# Terrarium.net
KiCad netlist of a schematic drawn in EAGLE
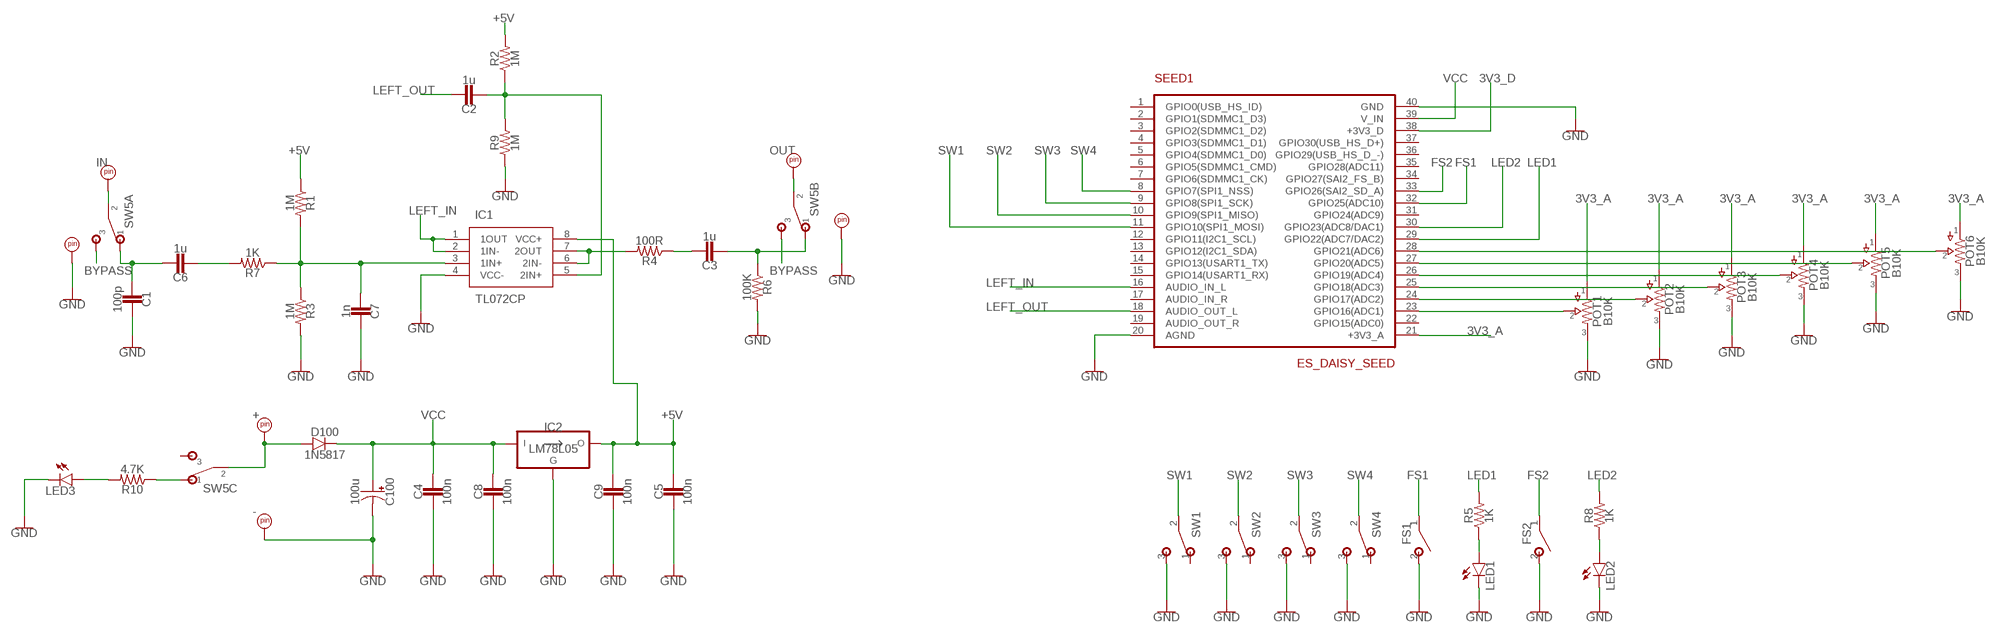
[diagram p0: schematic, sheet 1]

(export (version "E")
  (design (tool "Eeschema 10.0.6"))
  (components
    (comp (ref "C1")
      (value "100p")
      (footprint "eagle-import:5MM")
      (libsource (lib "eagle-import") (part "CAP.2"))
    )
    (comp (ref "C2")
      (value "1u")
      (footprint "eagle-import:.33UF+")
      (libsource (lib "eagle-import") (part "CAP.5"))
    )
    (comp (ref "C3")
      (value "1u")
      (footprint "eagle-import:.33UF+")
      (libsource (lib "eagle-import") (part "CAP.5"))
    )
    (comp (ref "C4")
      (value "100n")
      (footprint "eagle-import:5MM")
      (libsource (lib "eagle-import") (part "CAP.2"))
    )
    (comp (ref "C5")
      (value "100n")
      (footprint "eagle-import:5MM")
      (libsource (lib "eagle-import") (part "CAP.2"))
    )
    (comp (ref "C6")
      (value "1u")
      (footprint "eagle-import:.33UF+")
      (libsource (lib "eagle-import") (part "CAP.5"))
    )
    (comp (ref "C7")
      (value "1n")
      (footprint "eagle-import:5MM")
      (libsource (lib "eagle-import") (part "CAP.2"))
    )
    (comp (ref "C8")
      (value "100n")
      (footprint "eagle-import:5MM")
      (libsource (lib "eagle-import") (part "CAP.2"))
    )
    (comp (ref "C9")
      (value "100n")
      (footprint "eagle-import:5MM")
      (libsource (lib "eagle-import") (part "CAP.2"))
    )
    (comp (ref "C100")
      (value "100u")
      (footprint "eagle-import:050_2.5MM.2")
      (libsource (lib "eagle-import") (part "5.0_MM.4"))
    )
    (comp (ref "D100")
      (value "1N5817")
      (footprint "eagle-import:DO41-3")
      (libsource (lib "eagle-import") (part "DO41.3"))
    )
    (comp (ref "FS1")
      (value "SPST")
      (footprint "eagle-import:SPST")
      (libsource (lib "eagle-import") (part "SPST"))
    )
    (comp (ref "FS2")
      (value "SPST")
      (footprint "eagle-import:SPST")
      (libsource (lib "eagle-import") (part "SPST"))
    )
    (comp (ref "GND")
      (value "PADRD")
      (footprint "eagle-import:UNLABELED")
      (fields (field (name "NM") "-"))
      (libsource (lib "eagle-import") (part "PADRD"))
    )
    (comp (ref "IC1")
      (value "TL072CP")
      (footprint "eagle-import:DIP794W53P254L959H508Q8N")
      (fields (field (name "MOUSER_PART_NUMBER") "595-TL072CP"))
      (libsource (lib "eagle-import") (part "TL072CP"))
    )
    (comp (ref "IC2")
      (value "LM78L05")
      (footprint "eagle-import:TO92-")
      (libsource (lib "eagle-import") (part "LM78L05"))
    )
    (comp (ref "IN")
      (value "PADRD")
      (footprint "eagle-import:UNLABELED")
      (fields (field (name "NM") "IN"))
      (libsource (lib "eagle-import") (part "PADRD"))
    )
    (comp (ref "IN_GND")
      (value "PADRD")
      (footprint "eagle-import:UNLABELED")
      (libsource (lib "eagle-import") (part "PADRD"))
    )
    (comp (ref "LED1")
      (value "LED.3")
      (footprint "eagle-import:3MM_2")
      (libsource (lib "eagle-import") (part "LED.3"))
    )
    (comp (ref "LED2")
      (value "LED.3")
      (footprint "eagle-import:3MM_2")
      (libsource (lib "eagle-import") (part "LED.3"))
    )
    (comp (ref "LED3")
      (value "LED.3")
      (footprint "eagle-import:3MM_2")
      (libsource (lib "eagle-import") (part "LED.3"))
    )
    (comp (ref "OUT")
      (value "PADRD")
      (footprint "eagle-import:UNLABELED")
      (fields (field (name "NM") "OUT"))
      (libsource (lib "eagle-import") (part "PADRD"))
    )
    (comp (ref "OUT_GND")
      (value "PADRD")
      (footprint "eagle-import:UNLABELED")
      (libsource (lib "eagle-import") (part "PADRD"))
    )
    (comp (ref "POT1")
      (value "B10K")
      (footprint "eagle-import:16MM_PADS.2")
      (libsource (lib "eagle-import") (part "16MM.5"))
    )
    (comp (ref "POT2")
      (value "B10K")
      (footprint "eagle-import:16MM_PADS.2")
      (libsource (lib "eagle-import") (part "16MM.5"))
    )
    (comp (ref "POT3")
      (value "B10K")
      (footprint "eagle-import:16MM_PADS.2")
      (libsource (lib "eagle-import") (part "16MM.5"))
    )
    (comp (ref "POT4")
      (value "B10K")
      (footprint "eagle-import:16MM_PADS.2")
      (libsource (lib "eagle-import") (part "16MM.5"))
    )
    (comp (ref "POT5")
      (value "B10K")
      (footprint "eagle-import:16MM_PADS.2")
      (libsource (lib "eagle-import") (part "16MM.5"))
    )
    (comp (ref "POT6")
      (value "B10K")
      (footprint "eagle-import:16MM_PADS.2")
      (libsource (lib "eagle-import") (part "16MM.5"))
    )
    (comp (ref "PWR")
      (value "PADRD")
      (footprint "eagle-import:UNLABELED")
      (fields (field (name "NM") "+"))
      (libsource (lib "eagle-import") (part "PADRD"))
    )
    (comp (ref "R1")
      (value "1M")
      (footprint "eagle-import:7.5MM.2")
      (libsource (lib "eagle-import") (part "R.3B"))
    )
    (comp (ref "R2")
      (value "1M")
      (footprint "eagle-import:7.5MM.2")
      (libsource (lib "eagle-import") (part "R.3B"))
    )
    (comp (ref "R3")
      (value "1M")
      (footprint "eagle-import:7.5MM.2")
      (libsource (lib "eagle-import") (part "R.3B"))
    )
    (comp (ref "R4")
      (value "100R")
      (footprint "eagle-import:7.5MM.2")
      (libsource (lib "eagle-import") (part "R.3B"))
    )
    (comp (ref "R5")
      (value "1K")
      (footprint "eagle-import:7.5MM.2")
      (libsource (lib "eagle-import") (part "R.3B"))
    )
    (comp (ref "R6")
      (value "100K")
      (footprint "eagle-import:7.5MM.2")
      (libsource (lib "eagle-import") (part "R.3B"))
    )
    (comp (ref "R7")
      (value "1K")
      (footprint "eagle-import:7.5MM.2")
      (libsource (lib "eagle-import") (part "R.3B"))
    )
    (comp (ref "R8")
      (value "1K")
      (footprint "eagle-import:7.5MM.2")
      (libsource (lib "eagle-import") (part "R.3B"))
    )
    (comp (ref "R9")
      (value "1M")
      (footprint "eagle-import:7.5MM.2")
      (libsource (lib "eagle-import") (part "R.3B"))
    )
    (comp (ref "R10")
      (value "4.7K")
      (footprint "eagle-import:7.5MM.2")
      (libsource (lib "eagle-import") (part "R.3B"))
    )
    (comp (ref "SEED1")
      (value "ES_DAISY_SEED")
      (footprint "eagle-import:ES_DAISY_SEED")
      (libsource (lib "eagle-import") (part "ES_DAISY_SEED"))
    )
    (comp (ref "SW1")
      (value "SPDT.1")
      (footprint "eagle-import:SPDT_SOLDER_LUG")
      (libsource (lib "eagle-import") (part "SPDT.1"))
    )
    (comp (ref "SW2")
      (value "SPDT.1")
      (footprint "eagle-import:SPDT_SOLDER_LUG")
      (libsource (lib "eagle-import") (part "SPDT.1"))
    )
    (comp (ref "SW3")
      (value "SPDT.1")
      (footprint "eagle-import:SPDT_SOLDER_LUG")
      (libsource (lib "eagle-import") (part "SPDT.1"))
    )
    (comp (ref "SW4")
      (value "SPDT.1")
      (footprint "eagle-import:SPDT_SOLDER_LUG")
      (libsource (lib "eagle-import") (part "SPDT.1"))
    )
    (comp (ref "SW5")
      (value "3PDTTOGGLE")
      (footprint "eagle-import:3PDT2")
      (libsource (lib "eagle-import") (part "3PDTTOGGLE"))
    )
  )
  (nets
    (net (code "1") (name "/+5V") (class "Default")
      (node (ref "C5") (pin "1") (pinfunction "1_1") (pintype "passive"))
      (node (ref "C9") (pin "1") (pinfunction "1_1") (pintype "passive"))
      (node (ref "IC1") (pin "8") (pinfunction "VCC+_8") (pintype "bidirectional"))
      (node (ref "IC2") (pin "3") (pinfunction "VO_3") (pintype "passive"))
      (node (ref "R1") (pin "1") (pinfunction "1_1") (pintype "passive"))
      (node (ref "R2") (pin "2") (pinfunction "2_2") (pintype "passive"))
    )
    (net (code "2") (name "/3V3_A") (class "Default")
      (node (ref "POT1") (pin "1") (pinfunction "1_1") (pintype "passive"))
      (node (ref "POT2") (pin "1") (pinfunction "1_1") (pintype "passive"))
      (node (ref "POT3") (pin "1") (pinfunction "1_1") (pintype "passive"))
      (node (ref "POT4") (pin "1") (pinfunction "1_1") (pintype "passive"))
      (node (ref "POT5") (pin "1") (pinfunction "1_1") (pintype "passive"))
      (node (ref "POT6") (pin "1") (pinfunction "1_1") (pintype "passive"))
      (node (ref "SEED1") (pin "21") (pinfunction "+3V3_A_21") (pintype "bidirectional"))
    )
    (net (code "3") (name "/3V3_D") (class "Default")
      (node (ref "SEED1") (pin "38") (pinfunction "+3V3_D_38") (pintype "bidirectional"))
    )
    (net (code "4") (name "/BYPASS") (class "Default")
      (node (ref "SW5") (pin "A3") (pinfunction "3_A3") (pintype "passive"))
      (node (ref "SW5") (pin "B3") (pinfunction "3_B3") (pintype "passive"))
    )
    (net (code "5") (name "/FS1") (class "Default")
      (node (ref "FS1") (pin "1") (pinfunction "P_1") (pintype "passive"))
      (node (ref "SEED1") (pin "32") (pinfunction "GPIO25(ADC10)_32") (pintype "bidirectional"))
    )
    (net (code "6") (name "/FS2") (class "Default")
      (node (ref "FS2") (pin "1") (pinfunction "P_1") (pintype "passive"))
      (node (ref "SEED1") (pin "33") (pinfunction "GPIO26(SAI2_SD_A)_33") (pintype "bidirectional"))
    )
    (net (code "7") (name "/LED1") (class "Default")
      (node (ref "R5") (pin "2") (pinfunction "2_2") (pintype "passive"))
      (node (ref "SEED1") (pin "29") (pinfunction "GPIO22(ADC7/DAC2)_29") (pintype "bidirectional"))
    )
    (net (code "8") (name "/LED2") (class "Default")
      (node (ref "R8") (pin "2") (pinfunction "2_2") (pintype "passive"))
      (node (ref "SEED1") (pin "30") (pinfunction "GPIO23(ADC8/DAC1)_30") (pintype "bidirectional"))
    )
    (net (code "9") (name "/LEFT_IN") (class "Default")
      (node (ref "IC1") (pin "1") (pinfunction "1OUT_1") (pintype "bidirectional"))
      (node (ref "IC1") (pin "2") (pinfunction "1IN-_2") (pintype "bidirectional"))
      (node (ref "SEED1") (pin "16") (pinfunction "AUDIO_IN_L_16") (pintype "bidirectional"))
    )
    (net (code "10") (name "/LEFT_OUT") (class "Default")
      (node (ref "C2") (pin "1") (pinfunction "1_1") (pintype "passive"))
      (node (ref "SEED1") (pin "18") (pinfunction "AUDIO_OUT_L_18") (pintype "bidirectional"))
    )
    (net (code "11") (name "/SW1") (class "Default")
      (node (ref "SEED1") (pin "11") (pinfunction "GPIO10(SPI1_MOSI)_11") (pintype "bidirectional"))
      (node (ref "SW1") (pin "2") (pinfunction "P_2") (pintype "passive"))
    )
    (net (code "12") (name "/SW2") (class "Default")
      (node (ref "SEED1") (pin "10") (pinfunction "GPIO9(SPI1_MISO)_10") (pintype "bidirectional"))
      (node (ref "SW2") (pin "2") (pinfunction "P_2") (pintype "passive"))
    )
    (net (code "13") (name "/SW3") (class "Default")
      (node (ref "SEED1") (pin "9") (pinfunction "GPIO8(SPI1_SCK)_9") (pintype "bidirectional"))
      (node (ref "SW3") (pin "2") (pinfunction "P_2") (pintype "passive"))
    )
    (net (code "14") (name "/SW4") (class "Default")
      (node (ref "SEED1") (pin "8") (pinfunction "GPIO7(SPI1_NSS)_8") (pintype "bidirectional"))
      (node (ref "SW4") (pin "2") (pinfunction "P_2") (pintype "passive"))
    )
    (net (code "15") (name "/VCC") (class "Default")
      (node (ref "C100") (pin "+") (pinfunction "+_+") (pintype "passive"))
      (node (ref "C4") (pin "1") (pinfunction "1_1") (pintype "passive"))
      (node (ref "C8") (pin "1") (pinfunction "1_1") (pintype "passive"))
      (node (ref "D100") (pin "C") (pinfunction "C_C") (pintype "passive"))
      (node (ref "IC2") (pin "1") (pinfunction "VI_1") (pintype "input"))
      (node (ref "SEED1") (pin "39") (pinfunction "V_IN_39") (pintype "bidirectional"))
    )
    (net (code "16") (name "GND") (class "Default")
      (node (ref "C1") (pin "1") (pinfunction "1_1") (pintype "passive"))
      (node (ref "C100") (pin "-") (pinfunction "-_-") (pintype "passive"))
      (node (ref "C4") (pin "2") (pinfunction "2_2") (pintype "passive"))
      (node (ref "C5") (pin "2") (pinfunction "2_2") (pintype "passive"))
      (node (ref "C7") (pin "1") (pinfunction "1_1") (pintype "passive"))
      (node (ref "C8") (pin "2") (pinfunction "2_2") (pintype "passive"))
      (node (ref "C9") (pin "2") (pinfunction "2_2") (pintype "passive"))
      (node (ref "FS1") (pin "2") (pinfunction "S_2") (pintype "passive"))
      (node (ref "FS2") (pin "2") (pinfunction "S_2") (pintype "passive"))
      (node (ref "GND") (pin "P$1") (pinfunction "P$1_P$1") (pintype "bidirectional"))
      (node (ref "IC1") (pin "4") (pinfunction "VCC-_4") (pintype "bidirectional"))
      (node (ref "IC2") (pin "2") (pinfunction "GND_2") (pintype "passive"))
      (node (ref "IN_GND") (pin "P$1") (pinfunction "P$1_P$1") (pintype "bidirectional"))
      (node (ref "LED1") (pin "P$1") (pinfunction "C_P$1") (pintype "passive"))
      (node (ref "LED2") (pin "P$1") (pinfunction "C_P$1") (pintype "passive"))
      (node (ref "LED3") (pin "P$1") (pinfunction "C_P$1") (pintype "passive"))
      (node (ref "OUT_GND") (pin "P$1") (pinfunction "P$1_P$1") (pintype "bidirectional"))
      (node (ref "POT1") (pin "3") (pinfunction "3_3") (pintype "passive"))
      (node (ref "POT2") (pin "3") (pinfunction "3_3") (pintype "passive"))
      (node (ref "POT3") (pin "3") (pinfunction "3_3") (pintype "passive"))
      (node (ref "POT4") (pin "3") (pinfunction "3_3") (pintype "passive"))
      (node (ref "POT5") (pin "3") (pinfunction "3_3") (pintype "passive"))
      (node (ref "POT6") (pin "3") (pinfunction "3_3") (pintype "passive"))
      (node (ref "R3") (pin "2") (pinfunction "2_2") (pintype "passive"))
      (node (ref "R6") (pin "2") (pinfunction "2_2") (pintype "passive"))
      (node (ref "R9") (pin "1") (pinfunction "1_1") (pintype "passive"))
      (node (ref "SEED1") (pin "20") (pinfunction "AGND_20") (pintype "bidirectional"))
      (node (ref "SEED1") (pin "40") (pinfunction "GND_40") (pintype "bidirectional"))
      (node (ref "SW1") (pin "3") (pinfunction "S_3") (pintype "passive"))
      (node (ref "SW2") (pin "3") (pinfunction "S_3") (pintype "passive"))
      (node (ref "SW3") (pin "3") (pinfunction "S_3") (pintype "passive"))
      (node (ref "SW4") (pin "3") (pinfunction "S_3") (pintype "passive"))
    )
    (net (code "17") (name "Net-(C3-Pad1)") (class "Default")
      (node (ref "C3") (pin "1") (pinfunction "1_1") (pintype "passive"))
      (node (ref "R4") (pin "1") (pinfunction "1_1") (pintype "passive"))
    )
    (net (code "18") (name "Net-(C6-Pad2)") (class "Default")
      (node (ref "C6") (pin "2") (pinfunction "2_2") (pintype "passive"))
      (node (ref "R7") (pin "2") (pinfunction "2_2") (pintype "passive"))
    )
    (net (code "19") (name "Net-(IC1-1IN+)") (class "Default")
      (node (ref "C7") (pin "2") (pinfunction "2_2") (pintype "passive"))
      (node (ref "IC1") (pin "3") (pinfunction "1IN+_3") (pintype "bidirectional"))
      (node (ref "R1") (pin "2") (pinfunction "2_2") (pintype "passive"))
      (node (ref "R3") (pin "1") (pinfunction "1_1") (pintype "passive"))
      (node (ref "R7") (pin "1") (pinfunction "1_1") (pintype "passive"))
    )
    (net (code "20") (name "Net-(IC1-2IN+)") (class "Default")
      (node (ref "C2") (pin "2") (pinfunction "2_2") (pintype "passive"))
      (node (ref "IC1") (pin "5") (pinfunction "2IN+_5") (pintype "bidirectional"))
      (node (ref "R2") (pin "1") (pinfunction "1_1") (pintype "passive"))
      (node (ref "R9") (pin "2") (pinfunction "2_2") (pintype "passive"))
    )
    (net (code "21") (name "Net-(IC1-2IN-)") (class "Default")
      (node (ref "IC1") (pin "6") (pinfunction "2IN-_6") (pintype "bidirectional"))
      (node (ref "IC1") (pin "7") (pinfunction "2OUT_7") (pintype "bidirectional"))
      (node (ref "R4") (pin "2") (pinfunction "2_2") (pintype "passive"))
    )
    (net (code "22") (name "Net-(LED1-A)") (class "Default")
      (node (ref "LED1") (pin "ANODE") (pinfunction "A_ANODE") (pintype "passive"))
      (node (ref "R5") (pin "1") (pinfunction "1_1") (pintype "passive"))
    )
    (net (code "23") (name "Net-(LED2-A)") (class "Default")
      (node (ref "LED2") (pin "ANODE") (pinfunction "A_ANODE") (pintype "passive"))
      (node (ref "R8") (pin "1") (pinfunction "1_1") (pintype "passive"))
    )
    (net (code "24") (name "Net-(LED3-A)") (class "Default")
      (node (ref "LED3") (pin "ANODE") (pinfunction "A_ANODE") (pintype "passive"))
      (node (ref "R10") (pin "2") (pinfunction "2_2") (pintype "passive"))
    )
    (net (code "25") (name "Net-(SEED1-GPIO16(ADC1))") (class "Default")
      (node (ref "POT1") (pin "2") (pinfunction "2_2") (pintype "passive"))
      (node (ref "SEED1") (pin "23") (pinfunction "GPIO16(ADC1)_23") (pintype "bidirectional"))
    )
    (net (code "26") (name "Net-(SEED1-GPIO17(ADC2))") (class "Default")
      (node (ref "POT2") (pin "2") (pinfunction "2_2") (pintype "passive"))
      (node (ref "SEED1") (pin "24") (pinfunction "GPIO17(ADC2)_24") (pintype "bidirectional"))
    )
    (net (code "27") (name "Net-(SEED1-GPIO18(ADC3))") (class "Default")
      (node (ref "POT3") (pin "2") (pinfunction "2_2") (pintype "passive"))
      (node (ref "SEED1") (pin "25") (pinfunction "GPIO18(ADC3)_25") (pintype "bidirectional"))
    )
    (net (code "28") (name "Net-(SEED1-GPIO19(ADC4))") (class "Default")
      (node (ref "POT4") (pin "2") (pinfunction "2_2") (pintype "passive"))
      (node (ref "SEED1") (pin "26") (pinfunction "GPIO19(ADC4)_26") (pintype "bidirectional"))
    )
    (net (code "29") (name "Net-(SEED1-GPIO20(ADC5))") (class "Default")
      (node (ref "POT5") (pin "2") (pinfunction "2_2") (pintype "passive"))
      (node (ref "SEED1") (pin "27") (pinfunction "GPIO20(ADC5)_27") (pintype "bidirectional"))
    )
    (net (code "30") (name "Net-(SEED1-GPIO21(ADC6))") (class "Default")
      (node (ref "POT6") (pin "2") (pinfunction "2_2") (pintype "passive"))
      (node (ref "SEED1") (pin "28") (pinfunction "GPIO21(ADC6)_28") (pintype "bidirectional"))
    )
    (net (code "31") (name "Net-(SW5A-1)") (class "Default")
      (node (ref "C1") (pin "2") (pinfunction "2_2") (pintype "passive"))
      (node (ref "C6") (pin "1") (pinfunction "1_1") (pintype "passive"))
      (node (ref "SW5") (pin "A1") (pinfunction "1_A1") (pintype "passive"))
    )
    (net (code "32") (name "Net-(SW5A-2)") (class "Default")
      (node (ref "IN") (pin "P$1") (pinfunction "P$1_P$1") (pintype "bidirectional"))
      (node (ref "SW5") (pin "A2") (pinfunction "2_A2") (pintype "passive"))
    )
    (net (code "33") (name "Net-(SW5B-1)") (class "Default")
      (node (ref "C3") (pin "2") (pinfunction "2_2") (pintype "passive"))
      (node (ref "R6") (pin "1") (pinfunction "1_1") (pintype "passive"))
      (node (ref "SW5") (pin "B1") (pinfunction "1_B1") (pintype "passive"))
    )
    (net (code "34") (name "Net-(SW5B-2)") (class "Default")
      (node (ref "OUT") (pin "P$1") (pinfunction "P$1_P$1") (pintype "bidirectional"))
      (node (ref "SW5") (pin "B2") (pinfunction "2_B2") (pintype "passive"))
    )
    (net (code "35") (name "Net-(SW5C-1)") (class "Default")
      (node (ref "R10") (pin "1") (pinfunction "1_1") (pintype "passive"))
      (node (ref "SW5") (pin "C1") (pinfunction "1_C1") (pintype "passive"))
    )
    (net (code "36") (name "Net-(SW5C-2)") (class "Default")
      (node (ref "D100") (pin "A") (pinfunction "A_A") (pintype "passive"))
      (node (ref "PWR") (pin "P$1") (pinfunction "P$1_P$1") (pintype "bidirectional"))
      (node (ref "SW5") (pin "C2") (pinfunction "2_C2") (pintype "passive"))
    )
    (net (code "37") (name "unconnected-(SEED1-AUDIO_IN_R-Pad17)") (class "Default")
      (node (ref "SEED1") (pin "17") (pinfunction "AUDIO_IN_R_17") (pintype "bidirectional"))
    )
    (net (code "38") (name "unconnected-(SEED1-AUDIO_OUT_R-Pad19)") (class "Default")
      (node (ref "SEED1") (pin "19") (pinfunction "AUDIO_OUT_R_19") (pintype "bidirectional"))
    )
    (net (code "39") (name "unconnected-(SEED1-GPIO0(USB_HS_ID)-Pad1)") (class "Default")
      (node (ref "SEED1") (pin "1") (pinfunction "GPIO0(USB_HS_ID)_1") (pintype "bidirectional"))
    )
    (net (code "40") (name "unconnected-(SEED1-GPIO1(SDMMC1_D3)-Pad2)") (class "Default")
      (node (ref "SEED1") (pin "2") (pinfunction "GPIO1(SDMMC1_D3)_2") (pintype "bidirectional"))
    )
    (net (code "41") (name "unconnected-(SEED1-GPIO2(SDMMC1_D2)-Pad3)") (class "Default")
      (node (ref "SEED1") (pin "3") (pinfunction "GPIO2(SDMMC1_D2)_3") (pintype "bidirectional"))
    )
    (net (code "42") (name "unconnected-(SEED1-GPIO3(SDMMC1_D1)-Pad4)") (class "Default")
      (node (ref "SEED1") (pin "4") (pinfunction "GPIO3(SDMMC1_D1)_4") (pintype "bidirectional"))
    )
    (net (code "43") (name "unconnected-(SEED1-GPIO4(SDMMC1_D0)-Pad5)") (class "Default")
      (node (ref "SEED1") (pin "5") (pinfunction "GPIO4(SDMMC1_D0)_5") (pintype "bidirectional"))
    )
    (net (code "44") (name "unconnected-(SEED1-GPIO5(SDMMC1_CMD)-Pad6)") (class "Default")
      (node (ref "SEED1") (pin "6") (pinfunction "GPIO5(SDMMC1_CMD)_6") (pintype "bidirectional"))
    )
    (net (code "45") (name "unconnected-(SEED1-GPIO6(SDMMC1_CK)-Pad7)") (class "Default")
      (node (ref "SEED1") (pin "7") (pinfunction "GPIO6(SDMMC1_CK)_7") (pintype "bidirectional"))
    )
    (net (code "46") (name "unconnected-(SEED1-GPIO11(I2C1_SCL)-Pad12)") (class "Default")
      (node (ref "SEED1") (pin "12") (pinfunction "GPIO11(I2C1_SCL)_12") (pintype "bidirectional"))
    )
    (net (code "47") (name "unconnected-(SEED1-GPIO12(I2C1_SDA)-Pad13)") (class "Default")
      (node (ref "SEED1") (pin "13") (pinfunction "GPIO12(I2C1_SDA)_13") (pintype "bidirectional"))
    )
    (net (code "48") (name "unconnected-(SEED1-GPIO13(USART1_TX)-Pad14)") (class "Default")
      (node (ref "SEED1") (pin "14") (pinfunction "GPIO13(USART1_TX)_14") (pintype "bidirectional"))
    )
    (net (code "49") (name "unconnected-(SEED1-GPIO14(USART1_RX)-Pad15)") (class "Default")
      (node (ref "SEED1") (pin "15") (pinfunction "GPIO14(USART1_RX)_15") (pintype "bidirectional"))
    )
    (net (code "50") (name "unconnected-(SEED1-GPIO15(ADC0)-Pad22)") (class "Default")
      (node (ref "SEED1") (pin "22") (pinfunction "GPIO15(ADC0)_22") (pintype "bidirectional"))
    )
    (net (code "51") (name "unconnected-(SEED1-GPIO24(ADC9)-Pad31)") (class "Default")
      (node (ref "SEED1") (pin "31") (pinfunction "GPIO24(ADC9)_31") (pintype "bidirectional"))
    )
    (net (code "52") (name "unconnected-(SEED1-GPIO27(SAI2_FS_B)-Pad34)") (class "Default")
      (node (ref "SEED1") (pin "34") (pinfunction "GPIO27(SAI2_FS_B)_34") (pintype "bidirectional"))
    )
    (net (code "53") (name "unconnected-(SEED1-GPIO28(ADC11)-Pad35)") (class "Default")
      (node (ref "SEED1") (pin "35") (pinfunction "GPIO28(ADC11)_35") (pintype "bidirectional"))
    )
    (net (code "54") (name "unconnected-(SEED1-GPIO29(USB_HS_D_-)-Pad36)") (class "Default")
      (node (ref "SEED1") (pin "36") (pinfunction "GPIO29(USB_HS_D_-)_36") (pintype "bidirectional"))
    )
    (net (code "55") (name "unconnected-(SEED1-GPIO30(USB_HS_D+)-Pad37)") (class "Default")
      (node (ref "SEED1") (pin "37") (pinfunction "GPIO30(USB_HS_D+)_37") (pintype "bidirectional"))
    )
    (net (code "56") (name "unconnected-(SW1-O-Pad1)") (class "Default")
      (node (ref "SW1") (pin "1") (pinfunction "O_1") (pintype "passive"))
    )
    (net (code "57") (name "unconnected-(SW2-O-Pad1)") (class "Default")
      (node (ref "SW2") (pin "1") (pinfunction "O_1") (pintype "passive"))
    )
    (net (code "58") (name "unconnected-(SW3-O-Pad1)") (class "Default")
      (node (ref "SW3") (pin "1") (pinfunction "O_1") (pintype "passive"))
    )
    (net (code "59") (name "unconnected-(SW4-O-Pad1)") (class "Default")
      (node (ref "SW4") (pin "1") (pinfunction "O_1") (pintype "passive"))
    )
    (net (code "60") (name "unconnected-(SW5C-3-PadC3)") (class "Default")
      (node (ref "SW5") (pin "C3") (pinfunction "3_C3") (pintype "passive"))
    )
  )
)
